# core.net
KiCad netlist of a schematic drawn in EAGLE
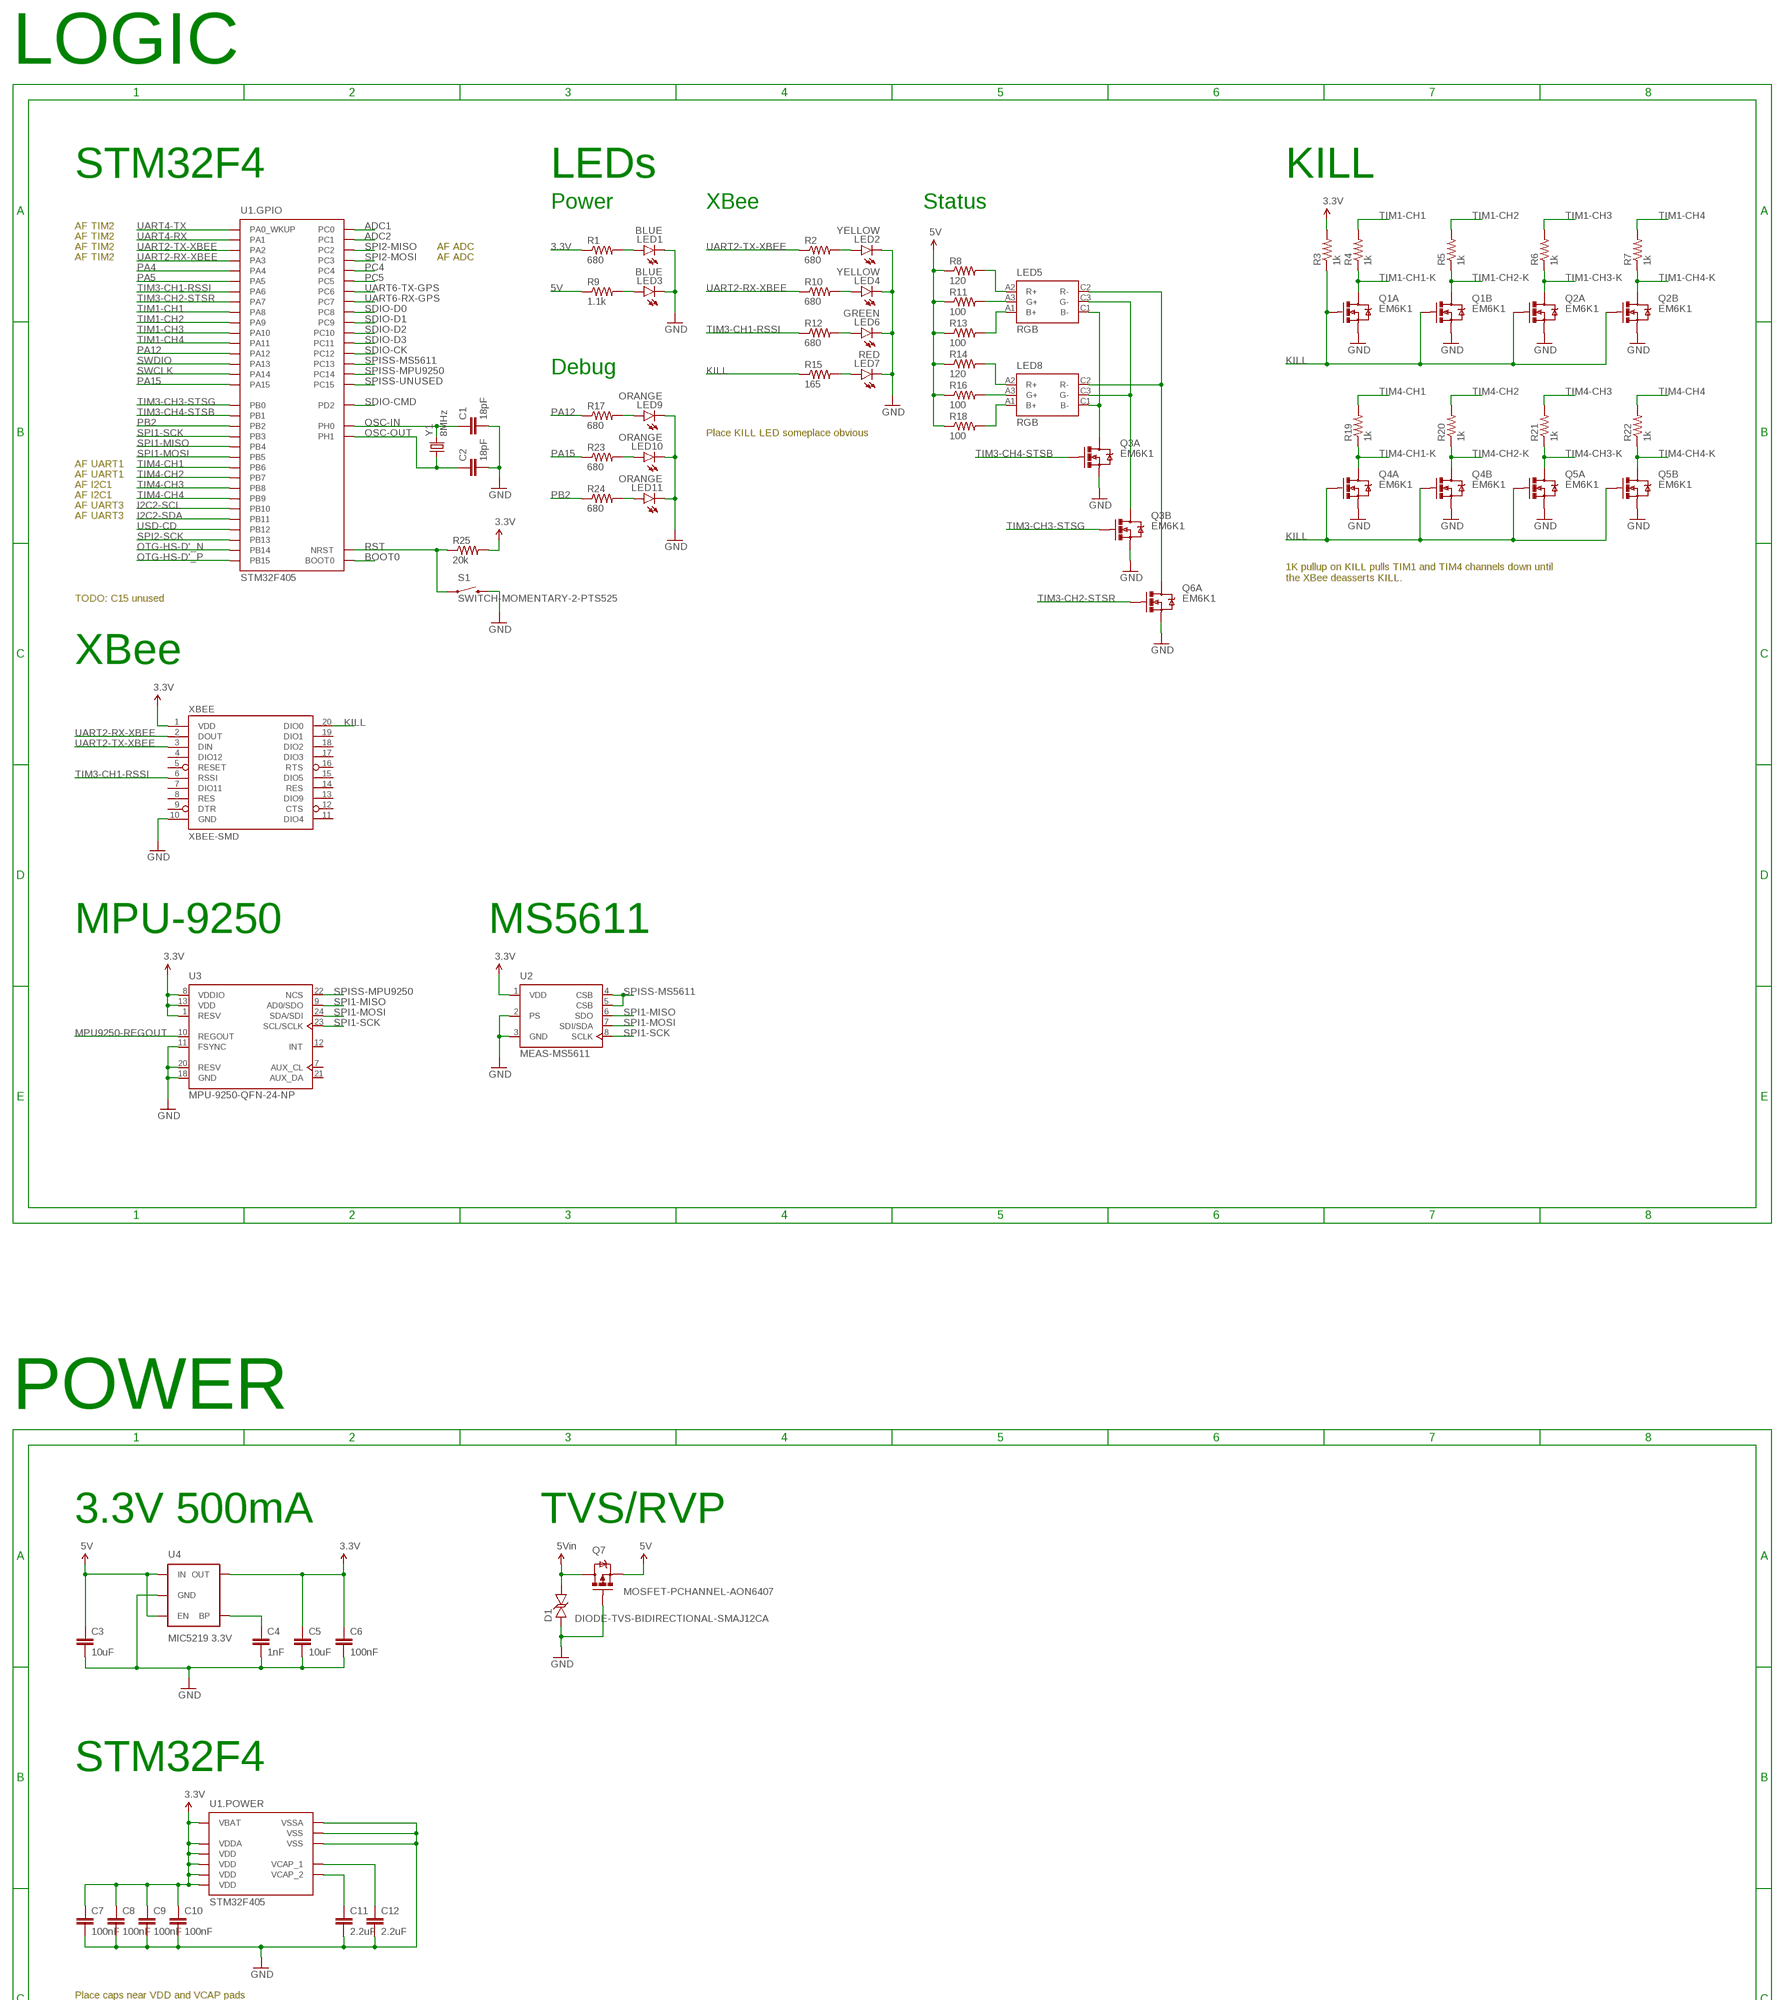
[diagram p0: schematic, sheet 1, part 1 of 2]
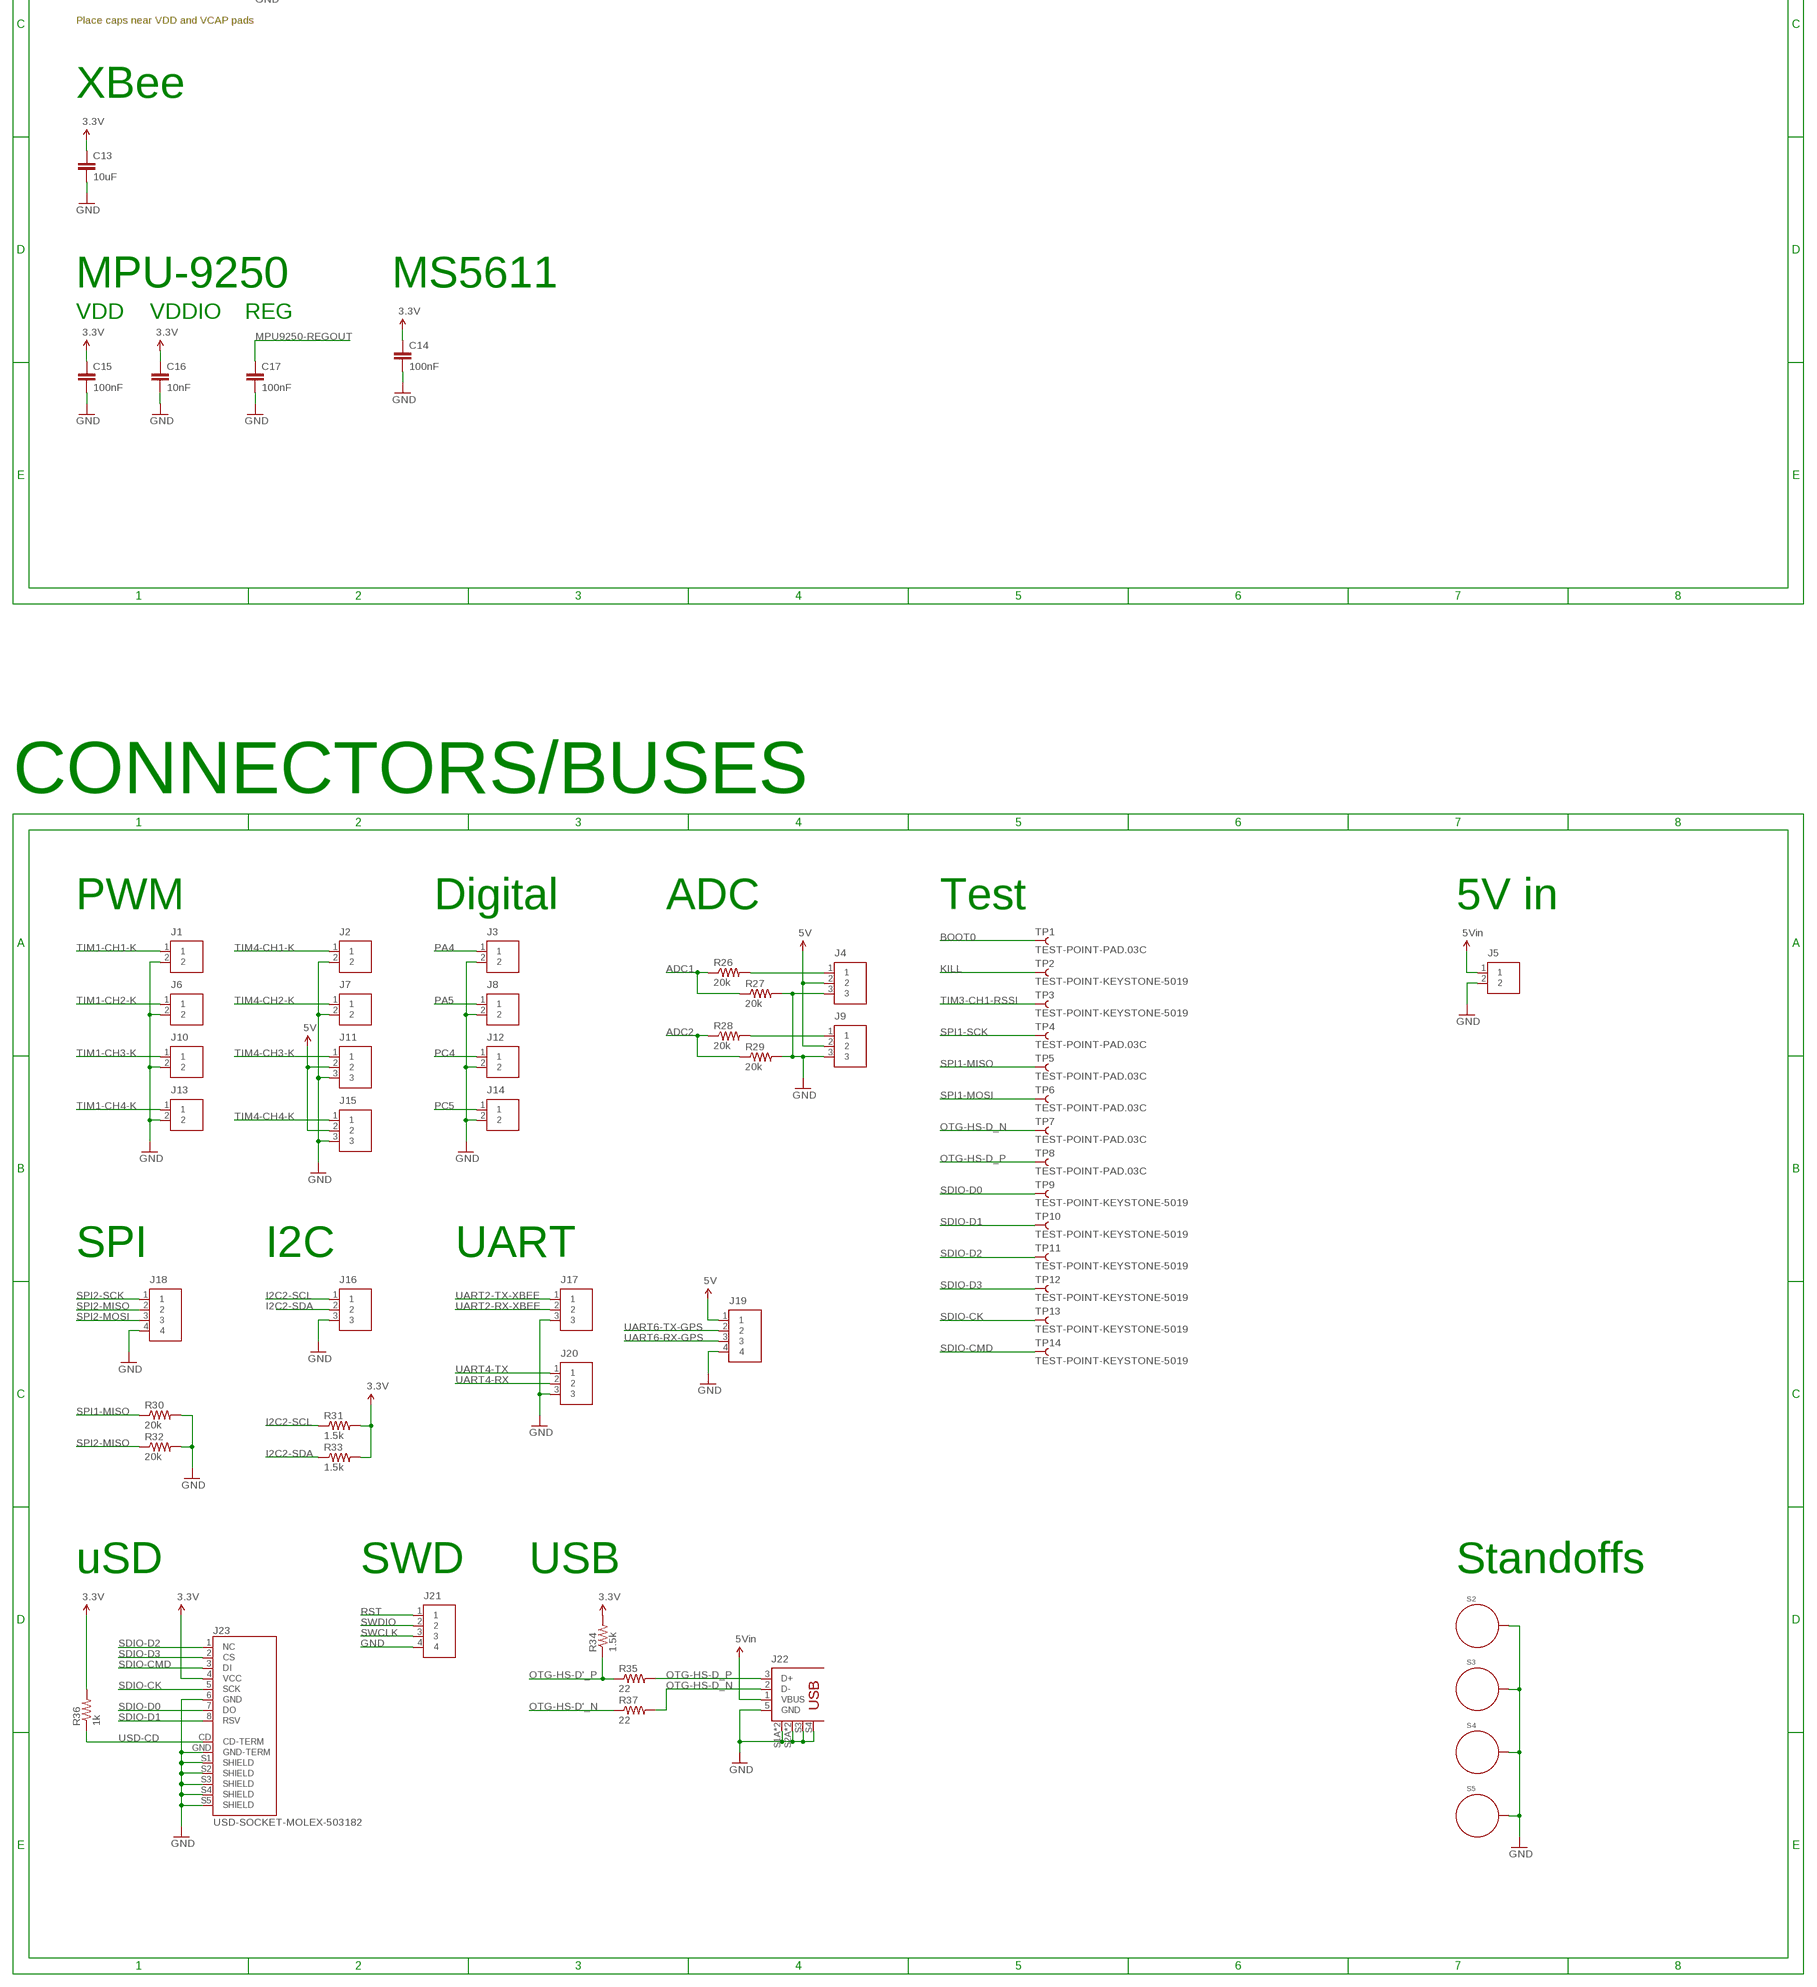
[diagram p1: schematic, sheet 1, part 2 of 2]

(export (version "E")
  (design (tool "Eeschema 10.0.6"))
  (components
    (comp (ref "C1")
      (value "18pF")
      (footprint "eagle-import:0603")
      (libsource (lib "eagle-import") (part "CAP-18PF-50V-5%(0603)"))
    )
    (comp (ref "C2")
      (value "18pF")
      (footprint "eagle-import:0603")
      (libsource (lib "eagle-import") (part "CAP-18PF-50V-5%(0603)"))
    )
    (comp (ref "C3")
      (value "10uF")
      (footprint "eagle-import:0805")
      (libsource (lib "eagle-import") (part "CAP-10UF-10V-10%(0805)"))
    )
    (comp (ref "C4")
      (value "1nF")
      (footprint "eagle-import:0603")
      (libsource (lib "eagle-import") (part "CAP-1NF-50V-10%(0603)"))
    )
    (comp (ref "C5")
      (value "10uF")
      (footprint "eagle-import:0805")
      (libsource (lib "eagle-import") (part "CAP-10UF-10V-10%(0805)"))
    )
    (comp (ref "C6")
      (value "100nF")
      (footprint "eagle-import:0603")
      (libsource (lib "eagle-import") (part "CAP-100NF-16V-10%(0603)"))
    )
    (comp (ref "C7")
      (value "100nF")
      (footprint "eagle-import:0603")
      (libsource (lib "eagle-import") (part "CAP-100NF-16V-10%(0603)"))
    )
    (comp (ref "C8")
      (value "100nF")
      (footprint "eagle-import:0603")
      (libsource (lib "eagle-import") (part "CAP-100NF-16V-10%(0603)"))
    )
    (comp (ref "C9")
      (value "100nF")
      (footprint "eagle-import:0603")
      (libsource (lib "eagle-import") (part "CAP-100NF-16V-10%(0603)"))
    )
    (comp (ref "C10")
      (value "100nF")
      (footprint "eagle-import:0603")
      (libsource (lib "eagle-import") (part "CAP-100NF-16V-10%(0603)"))
    )
    (comp (ref "C11")
      (value "2.2uF")
      (footprint "eagle-import:0603")
      (libsource (lib "eagle-import") (part "CAP-2.2UF-10V-10%(0603)"))
    )
    (comp (ref "C12")
      (value "2.2uF")
      (footprint "eagle-import:0603")
      (libsource (lib "eagle-import") (part "CAP-2.2UF-10V-10%(0603)"))
    )
    (comp (ref "C13")
      (value "10uF")
      (footprint "eagle-import:0805")
      (libsource (lib "eagle-import") (part "CAP-10UF-10V-10%(0805)"))
    )
    (comp (ref "C14")
      (value "100nF")
      (footprint "eagle-import:0603")
      (libsource (lib "eagle-import") (part "CAP-100NF-16V-10%(0603)"))
    )
    (comp (ref "C15")
      (value "100nF")
      (footprint "eagle-import:0603")
      (libsource (lib "eagle-import") (part "CAP-100NF-16V-10%(0603)"))
    )
    (comp (ref "C16")
      (value "10nF")
      (footprint "eagle-import:0603")
      (libsource (lib "eagle-import") (part "CAP-10NF-50V-10%(0603)"))
    )
    (comp (ref "C17")
      (value "100nF")
      (footprint "eagle-import:0603")
      (libsource (lib "eagle-import") (part "CAP-100NF-16V-10%(0603)"))
    )
    (comp (ref "D1")
      (value "DIODE-TVS-BIDIRECTIONAL-SMAJ12CA")
      (footprint "eagle-import:SMAJ")
      (libsource (lib "eagle-import") (part "DIODE-TVS-BIDIRECTIONAL-SMAJ12CA"))
    )
    (comp (ref "J1")
      (value "M02")
      (footprint "eagle-import:MOLEX-2MM-MICROLATCH-2POS-RA")
      (libsource (lib "eagle-import") (part "M02"))
    )
    (comp (ref "J2")
      (value "M02")
      (footprint "eagle-import:MOLEX-2MM-MICROLATCH-2POS-RA")
      (libsource (lib "eagle-import") (part "M02"))
    )
    (comp (ref "J3")
      (value "M02")
      (footprint "eagle-import:MOLEX-2MM-MICROLATCH-2POS-RA")
      (libsource (lib "eagle-import") (part "M02"))
    )
    (comp (ref "J4")
      (value "M03")
      (footprint "eagle-import:MOLEX-2MM-MICROLATCH-3POS-RA")
      (libsource (lib "eagle-import") (part "M03"))
    )
    (comp (ref "J5")
      (value "M02")
      (footprint "eagle-import:MOLEX-2MM-MICROLATCH-2POS-RA")
      (libsource (lib "eagle-import") (part "M02"))
    )
    (comp (ref "J6")
      (value "M02")
      (footprint "eagle-import:MOLEX-2MM-MICROLATCH-2POS-RA")
      (libsource (lib "eagle-import") (part "M02"))
    )
    (comp (ref "J7")
      (value "M02")
      (footprint "eagle-import:MOLEX-2MM-MICROLATCH-2POS-RA")
      (libsource (lib "eagle-import") (part "M02"))
    )
    (comp (ref "J8")
      (value "M02")
      (footprint "eagle-import:MOLEX-2MM-MICROLATCH-2POS-RA")
      (libsource (lib "eagle-import") (part "M02"))
    )
    (comp (ref "J9")
      (value "M03")
      (footprint "eagle-import:MOLEX-2MM-MICROLATCH-3POS-RA")
      (libsource (lib "eagle-import") (part "M03"))
    )
    (comp (ref "J10")
      (value "M02")
      (footprint "eagle-import:MOLEX-2MM-MICROLATCH-2POS-RA")
      (libsource (lib "eagle-import") (part "M02"))
    )
    (comp (ref "J11")
      (value "M03")
      (footprint "eagle-import:MOLEX-2MM-MICROLATCH-3POS-RA")
      (libsource (lib "eagle-import") (part "M03"))
    )
    (comp (ref "J12")
      (value "M02")
      (footprint "eagle-import:MOLEX-2MM-MICROLATCH-2POS-RA")
      (libsource (lib "eagle-import") (part "M02"))
    )
    (comp (ref "J13")
      (value "M02")
      (footprint "eagle-import:MOLEX-2MM-MICROLATCH-2POS-RA")
      (libsource (lib "eagle-import") (part "M02"))
    )
    (comp (ref "J14")
      (value "M02")
      (footprint "eagle-import:MOLEX-2MM-MICROLATCH-2POS-RA")
      (libsource (lib "eagle-import") (part "M02"))
    )
    (comp (ref "J15")
      (value "M03")
      (footprint "eagle-import:MOLEX-2MM-MICROLATCH-3POS-RA")
      (libsource (lib "eagle-import") (part "M03"))
    )
    (comp (ref "J16")
      (value "M03")
      (footprint "eagle-import:MOLEX-2MM-MICROLATCH-3POS-RA")
      (libsource (lib "eagle-import") (part "M03"))
    )
    (comp (ref "J17")
      (value "M03")
      (footprint "eagle-import:MOLEX-2MM-MICROLATCH-3POS-RA")
      (libsource (lib "eagle-import") (part "M03"))
    )
    (comp (ref "J18")
      (value "M04")
      (footprint "eagle-import:MOLEX-2MM-MICROLATCH-4POS-RA")
      (libsource (lib "eagle-import") (part "M04"))
    )
    (comp (ref "J19")
      (value "M04")
      (footprint "eagle-import:MOLEX-2MM-MICROLATCH-4POS-RA")
      (libsource (lib "eagle-import") (part "M04"))
    )
    (comp (ref "J20")
      (value "M03")
      (footprint "eagle-import:MOLEX-2MM-MICROLATCH-3POS-RA")
      (libsource (lib "eagle-import") (part "M03"))
    )
    (comp (ref "J21")
      (value "M04")
      (footprint "eagle-import:MOLEX-2MM-MICROLATCH-4POS-RA")
      (libsource (lib "eagle-import") (part "M04"))
    )
    (comp (ref "J22")
      (value "USB+SHIELD-MICROB-SMD-MOLEX")
      (footprint "eagle-import:USB-MICROB-SMD-MOLEX")
      (libsource (lib "eagle-import") (part "USB+SHIELD-MICROB-SMD-MOLEX"))
    )
    (comp (ref "J23")
      (value "USD-SOCKET-MOLEX-503182")
      (footprint "eagle-import:USD-SOCKET-PP-MOLEX-503182")
      (libsource (lib "eagle-import") (part "USD-SOCKET-MOLEX-503182"))
    )
    (comp (ref "LED1")
      (value "BLUE")
      (footprint "eagle-import:LED-0603")
      (libsource (lib "eagle-import") (part "LED-KINGBRIGHT-HELI-BLUE(0603)"))
    )
    (comp (ref "LED2")
      (value "YELLOW")
      (footprint "eagle-import:LED-0603")
      (libsource (lib "eagle-import") (part "LED-KINGBRIGHT-HELI-YELLOW(0603)"))
    )
    (comp (ref "LED3")
      (value "BLUE")
      (footprint "eagle-import:LED-0603")
      (libsource (lib "eagle-import") (part "LED-KINGBRIGHT-HELI-BLUE(0603)"))
    )
    (comp (ref "LED4")
      (value "YELLOW")
      (footprint "eagle-import:LED-0603")
      (libsource (lib "eagle-import") (part "LED-KINGBRIGHT-HELI-YELLOW(0603)"))
    )
    (comp (ref "LED5")
      (value "RGB")
      (footprint "eagle-import:PLCC-6")
      (libsource (lib "eagle-import") (part "OSRAM-MULTILED-RGB"))
    )
    (comp (ref "LED6")
      (value "GREEN")
      (footprint "eagle-import:LED-0603")
      (libsource (lib "eagle-import") (part "LED-KINGBRIGHT-HELI-GREEN(0603)"))
    )
    (comp (ref "LED7")
      (value "RED")
      (footprint "eagle-import:LED-0603")
      (libsource (lib "eagle-import") (part "LED-KINGBRIGHT-HELI-RED(0603)"))
    )
    (comp (ref "LED8")
      (value "RGB")
      (footprint "eagle-import:PLCC-6")
      (libsource (lib "eagle-import") (part "OSRAM-MULTILED-RGB"))
    )
    (comp (ref "LED9")
      (value "ORANGE")
      (footprint "eagle-import:LED-0603")
      (libsource (lib "eagle-import") (part "LED-KINGBRIGHT-HELI-ORANGE(0603)"))
    )
    (comp (ref "LED10")
      (value "ORANGE")
      (footprint "eagle-import:LED-0603")
      (libsource (lib "eagle-import") (part "LED-KINGBRIGHT-HELI-ORANGE(0603)"))
    )
    (comp (ref "LED11")
      (value "ORANGE")
      (footprint "eagle-import:LED-0603")
      (libsource (lib "eagle-import") (part "LED-KINGBRIGHT-HELI-ORANGE(0603)"))
    )
    (comp (ref "Q1")
      (value "EM6K1")
      (footprint "eagle-import:SOT-666")
      (libsource (lib "eagle-import") (part "MOSFET-NCHANNEL-DUAL-EM6K1"))
    )
    (comp (ref "Q2")
      (value "EM6K1")
      (footprint "eagle-import:SOT-666")
      (libsource (lib "eagle-import") (part "MOSFET-NCHANNEL-DUAL-EM6K1"))
    )
    (comp (ref "Q3")
      (value "EM6K1")
      (footprint "eagle-import:SOT-666")
      (libsource (lib "eagle-import") (part "MOSFET-NCHANNEL-DUAL-EM6K1"))
    )
    (comp (ref "Q4")
      (value "EM6K1")
      (footprint "eagle-import:SOT-666")
      (libsource (lib "eagle-import") (part "MOSFET-NCHANNEL-DUAL-EM6K1"))
    )
    (comp (ref "Q5")
      (value "EM6K1")
      (footprint "eagle-import:SOT-666")
      (libsource (lib "eagle-import") (part "MOSFET-NCHANNEL-DUAL-EM6K1"))
    )
    (comp (ref "Q6")
      (value "EM6K1")
      (footprint "eagle-import:SOT-666")
      (libsource (lib "eagle-import") (part "MOSFET-NCHANNEL-DUAL-EM6K1"))
    )
    (comp (ref "Q7")
      (value "MOSFET-PCHANNEL-AON6407")
      (footprint "eagle-import:DFN5X6")
      (libsource (lib "eagle-import") (part "MOSFET-PCHANNEL-AON6407"))
    )
    (comp (ref "R1")
      (value "680")
      (footprint "eagle-import:0603")
      (libsource (lib "eagle-import") (part "RES-680OHM-0.1W-5%(0603)"))
    )
    (comp (ref "R2")
      (value "680")
      (footprint "eagle-import:0603")
      (libsource (lib "eagle-import") (part "RES-680OHM-0.1W-5%(0603)"))
    )
    (comp (ref "R3")
      (value "1k")
      (footprint "eagle-import:0603")
      (libsource (lib "eagle-import") (part "RES-1KOHM-0.1W-5%(0603)"))
    )
    (comp (ref "R4")
      (value "1k")
      (footprint "eagle-import:0603")
      (libsource (lib "eagle-import") (part "RES-1KOHM-0.1W-5%(0603)"))
    )
    (comp (ref "R5")
      (value "1k")
      (footprint "eagle-import:0603")
      (libsource (lib "eagle-import") (part "RES-1KOHM-0.1W-5%(0603)"))
    )
    (comp (ref "R6")
      (value "1k")
      (footprint "eagle-import:0603")
      (libsource (lib "eagle-import") (part "RES-1KOHM-0.1W-5%(0603)"))
    )
    (comp (ref "R7")
      (value "1k")
      (footprint "eagle-import:0603")
      (libsource (lib "eagle-import") (part "RES-1KOHM-0.1W-5%(0603)"))
    )
    (comp (ref "R8")
      (value "120")
      (footprint "eagle-import:0603")
      (libsource (lib "eagle-import") (part "RES-120OHM-0.1W-5%(0603)"))
    )
    (comp (ref "R9")
      (value "1.1k")
      (footprint "eagle-import:0603")
      (libsource (lib "eagle-import") (part "RES-1.1KOHM-0.1W-5%(0603)"))
    )
    (comp (ref "R10")
      (value "680")
      (footprint "eagle-import:0603")
      (libsource (lib "eagle-import") (part "RES-680OHM-0.1W-5%(0603)"))
    )
    (comp (ref "R11")
      (value "100")
      (footprint "eagle-import:0603")
      (libsource (lib "eagle-import") (part "RES-100OHM-0.1W-5%(0603)"))
    )
    (comp (ref "R12")
      (value "680")
      (footprint "eagle-import:0603")
      (libsource (lib "eagle-import") (part "RES-680OHM-0.1W-5%(0603)"))
    )
    (comp (ref "R13")
      (value "100")
      (footprint "eagle-import:0603")
      (libsource (lib "eagle-import") (part "RES-100OHM-0.1W-5%(0603)"))
    )
    (comp (ref "R14")
      (value "120")
      (footprint "eagle-import:0603")
      (libsource (lib "eagle-import") (part "RES-120OHM-0.1W-5%(0603)"))
    )
    (comp (ref "R15")
      (value "165")
      (footprint "eagle-import:0603")
      (libsource (lib "eagle-import") (part "RES-165OHM-0.1W-1%(0603)"))
    )
    (comp (ref "R16")
      (value "100")
      (footprint "eagle-import:0603")
      (libsource (lib "eagle-import") (part "RES-100OHM-0.1W-5%(0603)"))
    )
    (comp (ref "R17")
      (value "680")
      (footprint "eagle-import:0603")
      (libsource (lib "eagle-import") (part "RES-680OHM-0.1W-5%(0603)"))
    )
    (comp (ref "R18")
      (value "100")
      (footprint "eagle-import:0603")
      (libsource (lib "eagle-import") (part "RES-100OHM-0.1W-5%(0603)"))
    )
    (comp (ref "R19")
      (value "1k")
      (footprint "eagle-import:0603")
      (libsource (lib "eagle-import") (part "RES-1KOHM-0.1W-5%(0603)"))
    )
    (comp (ref "R20")
      (value "1k")
      (footprint "eagle-import:0603")
      (libsource (lib "eagle-import") (part "RES-1KOHM-0.1W-5%(0603)"))
    )
    (comp (ref "R21")
      (value "1k")
      (footprint "eagle-import:0603")
      (libsource (lib "eagle-import") (part "RES-1KOHM-0.1W-5%(0603)"))
    )
    (comp (ref "R22")
      (value "1k")
      (footprint "eagle-import:0603")
      (libsource (lib "eagle-import") (part "RES-1KOHM-0.1W-5%(0603)"))
    )
    (comp (ref "R23")
      (value "680")
      (footprint "eagle-import:0603")
      (libsource (lib "eagle-import") (part "RES-680OHM-0.1W-5%(0603)"))
    )
    (comp (ref "R24")
      (value "680")
      (footprint "eagle-import:0603")
      (libsource (lib "eagle-import") (part "RES-680OHM-0.1W-5%(0603)"))
    )
    (comp (ref "R25")
      (value "20k")
      (footprint "eagle-import:0603")
      (libsource (lib "eagle-import") (part "RES-20KOHM-0.1W-1%(0603)"))
    )
    (comp (ref "R26")
      (value "20k")
      (footprint "eagle-import:0603")
      (libsource (lib "eagle-import") (part "RES-20KOHM-0.1W-0.1%(0603)"))
    )
    (comp (ref "R27")
      (value "20k")
      (footprint "eagle-import:0603")
      (libsource (lib "eagle-import") (part "RES-20KOHM-0.1W-0.1%(0603)"))
    )
    (comp (ref "R28")
      (value "20k")
      (footprint "eagle-import:0603")
      (libsource (lib "eagle-import") (part "RES-20KOHM-0.1W-0.1%(0603)"))
    )
    (comp (ref "R29")
      (value "20k")
      (footprint "eagle-import:0603")
      (libsource (lib "eagle-import") (part "RES-20KOHM-0.1W-0.1%(0603)"))
    )
    (comp (ref "R30")
      (value "20k")
      (footprint "eagle-import:0603")
      (libsource (lib "eagle-import") (part "RES-20KOHM-0.1W-1%(0603)"))
    )
    (comp (ref "R31")
      (value "1.5k")
      (footprint "eagle-import:0603")
      (libsource (lib "eagle-import") (part "RES-1.5KOHM-0.1W-5%(0603)"))
    )
    (comp (ref "R32")
      (value "20k")
      (footprint "eagle-import:0603")
      (libsource (lib "eagle-import") (part "RES-20KOHM-0.1W-1%(0603)"))
    )
    (comp (ref "R33")
      (value "1.5k")
      (footprint "eagle-import:0603")
      (libsource (lib "eagle-import") (part "RES-1.5KOHM-0.1W-5%(0603)"))
    )
    (comp (ref "R34")
      (value "1.5k")
      (footprint "eagle-import:0603")
      (libsource (lib "eagle-import") (part "RES-1.5KOHM-0.1W-5%(0603)"))
    )
    (comp (ref "R35")
      (value "22")
      (footprint "eagle-import:0603")
      (libsource (lib "eagle-import") (part "RES-22OHM-0.1W-5%(0603)"))
    )
    (comp (ref "R36")
      (value "1k")
      (footprint "eagle-import:0603")
      (libsource (lib "eagle-import") (part "RES-1KOHM-0.1W-5%(0603)"))
    )
    (comp (ref "R37")
      (value "22")
      (footprint "eagle-import:0603")
      (libsource (lib "eagle-import") (part "RES-22OHM-0.1W-5%(0603)"))
    )
    (comp (ref "S1")
      (value "SWITCH-MOMENTARY-2-PTS525")
      (footprint "eagle-import:TACTILE-SWITCH-SMD")
      (libsource (lib "eagle-import") (part "SWITCH-MOMENTARY-2-PTS525"))
    )
    (comp (ref "S2")
      (value "STANDOFF_ELECTRICAL-#4")
      (footprint "eagle-import:STANDOFF-ELECTRICAL-#4")
      (libsource (lib "eagle-import") (part "STANDOFF_ELECTRICAL-#4"))
    )
    (comp (ref "S3")
      (value "STANDOFF_ELECTRICAL-#4")
      (footprint "eagle-import:STANDOFF-ELECTRICAL-#4")
      (libsource (lib "eagle-import") (part "STANDOFF_ELECTRICAL-#4"))
    )
    (comp (ref "S4")
      (value "STANDOFF_ELECTRICAL-#4")
      (footprint "eagle-import:STANDOFF-ELECTRICAL-#4")
      (libsource (lib "eagle-import") (part "STANDOFF_ELECTRICAL-#4"))
    )
    (comp (ref "S5")
      (value "STANDOFF_ELECTRICAL-#4")
      (footprint "eagle-import:STANDOFF-ELECTRICAL-#4")
      (libsource (lib "eagle-import") (part "STANDOFF_ELECTRICAL-#4"))
    )
    (comp (ref "TP1")
      (value "TEST-POINT-PAD.03C")
      (footprint "eagle-import:PAD-.03C")
      (libsource (lib "eagle-import") (part "TEST-POINT-PAD.03C"))
    )
    (comp (ref "TP2")
      (value "TEST-POINT-KEYSTONE-5019")
      (footprint "eagle-import:PAD.15X.08")
      (libsource (lib "eagle-import") (part "TEST-POINT-KEYSTONE-5019"))
    )
    (comp (ref "TP3")
      (value "TEST-POINT-KEYSTONE-5019")
      (footprint "eagle-import:PAD.15X.08")
      (libsource (lib "eagle-import") (part "TEST-POINT-KEYSTONE-5019"))
    )
    (comp (ref "TP4")
      (value "TEST-POINT-PAD.03C")
      (footprint "eagle-import:PAD-.03C")
      (libsource (lib "eagle-import") (part "TEST-POINT-PAD.03C"))
    )
    (comp (ref "TP5")
      (value "TEST-POINT-PAD.03C")
      (footprint "eagle-import:PAD-.03C")
      (libsource (lib "eagle-import") (part "TEST-POINT-PAD.03C"))
    )
    (comp (ref "TP6")
      (value "TEST-POINT-PAD.03C")
      (footprint "eagle-import:PAD-.03C")
      (libsource (lib "eagle-import") (part "TEST-POINT-PAD.03C"))
    )
    (comp (ref "TP7")
      (value "TEST-POINT-PAD.03C")
      (footprint "eagle-import:PAD-.03C")
      (libsource (lib "eagle-import") (part "TEST-POINT-PAD.03C"))
    )
    (comp (ref "TP8")
      (value "TEST-POINT-PAD.03C")
      (footprint "eagle-import:PAD-.03C")
      (libsource (lib "eagle-import") (part "TEST-POINT-PAD.03C"))
    )
    (comp (ref "TP9")
      (value "TEST-POINT-KEYSTONE-5019")
      (footprint "eagle-import:PAD.15X.08")
      (libsource (lib "eagle-import") (part "TEST-POINT-KEYSTONE-5019"))
    )
    (comp (ref "TP10")
      (value "TEST-POINT-KEYSTONE-5019")
      (footprint "eagle-import:PAD.15X.08")
      (libsource (lib "eagle-import") (part "TEST-POINT-KEYSTONE-5019"))
    )
    (comp (ref "TP11")
      (value "TEST-POINT-KEYSTONE-5019")
      (footprint "eagle-import:PAD.15X.08")
      (libsource (lib "eagle-import") (part "TEST-POINT-KEYSTONE-5019"))
    )
    (comp (ref "TP12")
      (value "TEST-POINT-KEYSTONE-5019")
      (footprint "eagle-import:PAD.15X.08")
      (libsource (lib "eagle-import") (part "TEST-POINT-KEYSTONE-5019"))
    )
    (comp (ref "TP13")
      (value "TEST-POINT-KEYSTONE-5019")
      (footprint "eagle-import:PAD.15X.08")
      (libsource (lib "eagle-import") (part "TEST-POINT-KEYSTONE-5019"))
    )
    (comp (ref "TP14")
      (value "TEST-POINT-KEYSTONE-5019")
      (footprint "eagle-import:PAD.15X.08")
      (libsource (lib "eagle-import") (part "TEST-POINT-KEYSTONE-5019"))
    )
    (comp (ref "U1")
      (value "STM32F405")
      (footprint "eagle-import:LQFP-64-STM32F405")
      (libsource (lib "eagle-import") (part "STM32F405"))
    )
    (comp (ref "U2")
      (value "MEAS-MS5611")
      (footprint "eagle-import:MEAS-MS5611")
      (libsource (lib "eagle-import") (part "MEAS-MS5611"))
    )
    (comp (ref "U3")
      (value "MPU-9250-QFN-24-NP")
      (footprint "eagle-import:QFN-24-NP-3X3MM")
      (libsource (lib "eagle-import") (part "MPU-9250-QFN-24-NP"))
    )
    (comp (ref "U4")
      (value "MIC5219 3.3V")
      (footprint "eagle-import:SOT23-5")
      (libsource (lib "eagle-import") (part "V-REG-MIC5219-3.3V"))
    )
    (comp (ref "XBEE")
      (value "XBEE-SMD")
      (footprint "eagle-import:XBEE-SMD")
      (libsource (lib "eagle-import") (part "XBEE-SMD"))
    )
    (comp (ref "Y1")
      (value "8MHz")
      (footprint "eagle-import:CX532")
      (libsource (lib "eagle-import") (part "CRYSTAL-8MHZ-CX532"))
    )
  )
  (nets
    (net (code "1") (name "/ADC1") (class "Default")
      (node (ref "R26") (pin "1") (pinfunction "1_1") (pintype "passive"))
      (node (ref "R27") (pin "1") (pinfunction "1_1") (pintype "passive"))
      (node (ref "U1") (pin "8") (pinfunction "PC0_8") (pintype "bidirectional"))
    )
    (net (code "2") (name "/ADC2") (class "Default")
      (node (ref "R28") (pin "1") (pinfunction "1_1") (pintype "passive"))
      (node (ref "R29") (pin "1") (pinfunction "1_1") (pintype "passive"))
      (node (ref "U1") (pin "9") (pinfunction "PC1_9") (pintype "bidirectional"))
    )
    (net (code "3") (name "/BOOT0") (class "Default")
      (node (ref "TP1") (pin "1") (pinfunction "1_1") (pintype "bidirectional"))
      (node (ref "U1") (pin "60") (pinfunction "BOOT0_60") (pintype "bidirectional"))
    )
    (net (code "4") (name "/I2C2-SCL") (class "Default")
      (node (ref "J16") (pin "1") (pinfunction "1_1") (pintype "bidirectional"))
      (node (ref "R31") (pin "1") (pinfunction "1_1") (pintype "passive"))
      (node (ref "U1") (pin "29") (pinfunction "PB10_29") (pintype "bidirectional"))
    )
    (net (code "5") (name "/I2C2-SDA") (class "Default")
      (node (ref "J16") (pin "2") (pinfunction "2_2") (pintype "bidirectional"))
      (node (ref "R33") (pin "1") (pinfunction "1_1") (pintype "passive"))
      (node (ref "U1") (pin "30") (pinfunction "PB11_30") (pintype "bidirectional"))
    )
    (net (code "6") (name "/KILL") (class "Default")
      (node (ref "Q1") (pin "2") (pinfunction "G_2") (pintype "passive"))
      (node (ref "Q1") (pin "5") (pinfunction "G_5") (pintype "passive"))
      (node (ref "Q2") (pin "2") (pinfunction "G_2") (pintype "passive"))
      (node (ref "Q2") (pin "5") (pinfunction "G_5") (pintype "passive"))
      (node (ref "Q4") (pin "2") (pinfunction "G_2") (pintype "passive"))
      (node (ref "Q4") (pin "5") (pinfunction "G_5") (pintype "passive"))
      (node (ref "Q5") (pin "2") (pinfunction "G_2") (pintype "passive"))
      (node (ref "Q5") (pin "5") (pinfunction "G_5") (pintype "passive"))
      (node (ref "R15") (pin "1") (pinfunction "1_1") (pintype "passive"))
      (node (ref "R3") (pin "1") (pinfunction "1_1") (pintype "passive"))
      (node (ref "TP2") (pin "1") (pinfunction "1_1") (pintype "bidirectional"))
      (node (ref "XBEE") (pin "20") (pinfunction "DIO0_20") (pintype "bidirectional"))
    )
    (net (code "7") (name "/MPU9250-REGOUT") (class "Default")
      (node (ref "C17") (pin "2") (pinfunction "2_2") (pintype "passive"))
      (node (ref "U3") (pin "10") (pinfunction "REGOUT_10") (pintype "bidirectional"))
    )
    (net (code "8") (name "/OSC-IN") (class "Default")
      (node (ref "C1") (pin "2") (pinfunction "2_2") (pintype "passive"))
      (node (ref "U1") (pin "5") (pinfunction "PH0_5") (pintype "bidirectional"))
      (node (ref "Y1") (pin "2") (pinfunction "2_2") (pintype "passive"))
    )
    (net (code "9") (name "/OSC-OUT") (class "Default")
      (node (ref "C2") (pin "2") (pinfunction "2_2") (pintype "passive"))
      (node (ref "U1") (pin "6") (pinfunction "PH1_6") (pintype "bidirectional"))
      (node (ref "Y1") (pin "1") (pinfunction "1_1") (pintype "passive"))
    )
    (net (code "10") (name "/OTG-HS-D'_N") (class "Default")
      (node (ref "R37") (pin "1") (pinfunction "1_1") (pintype "passive"))
      (node (ref "U1") (pin "35") (pinfunction "PB14_35") (pintype "bidirectional"))
    )
    (net (code "11") (name "/OTG-HS-D'_P") (class "Default")
      (node (ref "R34") (pin "1") (pinfunction "1_1") (pintype "passive"))
      (node (ref "R35") (pin "1") (pinfunction "1_1") (pintype "passive"))
      (node (ref "U1") (pin "36") (pinfunction "PB15_36") (pintype "bidirectional"))
    )
    (net (code "12") (name "/OTG-HS-D_N") (class "Default")
      (node (ref "J22") (pin "2") (pinfunction "D-_2") (pintype "bidirectional"))
      (node (ref "R37") (pin "2") (pinfunction "2_2") (pintype "passive"))
      (node (ref "TP7") (pin "1") (pinfunction "1_1") (pintype "bidirectional"))
    )
    (net (code "13") (name "/OTG-HS-D_P") (class "Default")
      (node (ref "J22") (pin "3") (pinfunction "D+_3") (pintype "bidirectional"))
      (node (ref "R35") (pin "2") (pinfunction "2_2") (pintype "passive"))
      (node (ref "TP8") (pin "1") (pinfunction "1_1") (pintype "bidirectional"))
    )
    (net (code "14") (name "/PA4") (class "Default")
      (node (ref "J3") (pin "1") (pinfunction "1_1") (pintype "bidirectional"))
      (node (ref "U1") (pin "20") (pinfunction "PA4_20") (pintype "bidirectional"))
    )
    (net (code "15") (name "/PA5") (class "Default")
      (node (ref "J8") (pin "1") (pinfunction "1_1") (pintype "bidirectional"))
      (node (ref "U1") (pin "21") (pinfunction "PA5_21") (pintype "bidirectional"))
    )
    (net (code "16") (name "/PA12") (class "Default")
      (node (ref "R17") (pin "1") (pinfunction "1_1") (pintype "passive"))
      (node (ref "U1") (pin "45") (pinfunction "PA12_45") (pintype "bidirectional"))
    )
    (net (code "17") (name "/PA15") (class "Default")
      (node (ref "R23") (pin "1") (pinfunction "1_1") (pintype "passive"))
      (node (ref "U1") (pin "50") (pinfunction "PA15_50") (pintype "bidirectional"))
    )
    (net (code "18") (name "/PB2") (class "Default")
      (node (ref "R24") (pin "1") (pinfunction "1_1") (pintype "passive"))
      (node (ref "U1") (pin "28") (pinfunction "PB2_28") (pintype "bidirectional"))
    )
    (net (code "19") (name "/PC4") (class "Default")
      (node (ref "J12") (pin "1") (pinfunction "1_1") (pintype "bidirectional"))
      (node (ref "U1") (pin "24") (pinfunction "PC4_24") (pintype "bidirectional"))
    )
    (net (code "20") (name "/PC5") (class "Default")
      (node (ref "J14") (pin "1") (pinfunction "1_1") (pintype "bidirectional"))
      (node (ref "U1") (pin "25") (pinfunction "PC5_25") (pintype "bidirectional"))
    )
    (net (code "21") (name "/RST") (class "Default")
      (node (ref "J21") (pin "1") (pinfunction "1_1") (pintype "bidirectional"))
      (node (ref "R25") (pin "1") (pinfunction "1_1") (pintype "passive"))
      (node (ref "S1") (pin "1") (pinfunction "1_1") (pintype "passive"))
      (node (ref "S1") (pin "2") (pinfunction "1_2") (pintype "passive"))
      (node (ref "U1") (pin "7") (pinfunction "NRST_7") (pintype "bidirectional"))
    )
    (net (code "22") (name "/SDIO-CK") (class "Default")
      (node (ref "J23") (pin "5") (pinfunction "SCK_5") (pintype "bidirectional"))
      (node (ref "TP13") (pin "1") (pinfunction "1_1") (pintype "bidirectional"))
      (node (ref "U1") (pin "53") (pinfunction "PC12_53") (pintype "bidirectional"))
    )
    (net (code "23") (name "/SDIO-CMD") (class "Default")
      (node (ref "J23") (pin "3") (pinfunction "DI_3") (pintype "bidirectional"))
      (node (ref "TP14") (pin "1") (pinfunction "1_1") (pintype "bidirectional"))
      (node (ref "U1") (pin "54") (pinfunction "PD2_54") (pintype "bidirectional"))
    )
    (net (code "24") (name "/SDIO-D0") (class "Default")
      (node (ref "J23") (pin "7") (pinfunction "DO_7") (pintype "bidirectional"))
      (node (ref "TP9") (pin "1") (pinfunction "1_1") (pintype "bidirectional"))
      (node (ref "U1") (pin "39") (pinfunction "PC8_39") (pintype "bidirectional"))
    )
    (net (code "25") (name "/SDIO-D1") (class "Default")
      (node (ref "J23") (pin "8") (pinfunction "RSV_8") (pintype "bidirectional"))
      (node (ref "TP10") (pin "1") (pinfunction "1_1") (pintype "bidirectional"))
      (node (ref "U1") (pin "40") (pinfunction "PC9_40") (pintype "bidirectional"))
    )
    (net (code "26") (name "/SDIO-D2") (class "Default")
      (node (ref "J23") (pin "1") (pinfunction "NC_1") (pintype "bidirectional"))
      (node (ref "TP11") (pin "1") (pinfunction "1_1") (pintype "bidirectional"))
      (node (ref "U1") (pin "51") (pinfunction "PC10_51") (pintype "bidirectional"))
    )
    (net (code "27") (name "/SDIO-D3") (class "Default")
      (node (ref "J23") (pin "2") (pinfunction "CS_2") (pintype "bidirectional"))
      (node (ref "TP12") (pin "1") (pinfunction "1_1") (pintype "bidirectional"))
      (node (ref "U1") (pin "52") (pinfunction "PC11_52") (pintype "bidirectional"))
    )
    (net (code "28") (name "/SPI1-MISO") (class "Default")
      (node (ref "R30") (pin "1") (pinfunction "1_1") (pintype "passive"))
      (node (ref "TP5") (pin "1") (pinfunction "1_1") (pintype "bidirectional"))
      (node (ref "U1") (pin "56") (pinfunction "PB4_56") (pintype "bidirectional"))
      (node (ref "U2") (pin "6") (pinfunction "SDO_6") (pintype "output"))
      (node (ref "U3") (pin "9") (pinfunction "AD0/SDO_9") (pintype "bidirectional"))
    )
    (net (code "29") (name "/SPI1-MOSI") (class "Default")
      (node (ref "TP6") (pin "1") (pinfunction "1_1") (pintype "bidirectional"))
      (node (ref "U1") (pin "57") (pinfunction "PB5_57") (pintype "bidirectional"))
      (node (ref "U2") (pin "7") (pinfunction "SDI/SDA_7") (pintype "bidirectional"))
      (node (ref "U3") (pin "24") (pinfunction "SDA/SDI_24") (pintype "bidirectional"))
    )
    (net (code "30") (name "/SPI1-SCK") (class "Default")
      (node (ref "TP4") (pin "1") (pinfunction "1_1") (pintype "bidirectional"))
      (node (ref "U1") (pin "55") (pinfunction "PB3_55") (pintype "bidirectional"))
      (node (ref "U2") (pin "8") (pinfunction "SCLK_8") (pintype "input"))
      (node (ref "U3") (pin "23") (pinfunction "SCL/SCLK_23") (pintype "bidirectional"))
    )
    (net (code "31") (name "/SPI2-MISO") (class "Default")
      (node (ref "J18") (pin "2") (pinfunction "2_2") (pintype "bidirectional"))
      (node (ref "R32") (pin "1") (pinfunction "1_1") (pintype "passive"))
      (node (ref "U1") (pin "10") (pinfunction "PC2_10") (pintype "bidirectional"))
    )
    (net (code "32") (name "/SPI2-MOSI") (class "Default")
      (node (ref "J18") (pin "3") (pinfunction "3_3") (pintype "bidirectional"))
      (node (ref "U1") (pin "11") (pinfunction "PC3_11") (pintype "bidirectional"))
    )
    (net (code "33") (name "/SPI2-SCK") (class "Default")
      (node (ref "J18") (pin "1") (pinfunction "1_1") (pintype "bidirectional"))
      (node (ref "U1") (pin "34") (pinfunction "PB13_34") (pintype "bidirectional"))
    )
    (net (code "34") (name "/SPISS-MPU9250") (class "Default")
      (node (ref "U1") (pin "3") (pinfunction "PC14_3") (pintype "bidirectional"))
      (node (ref "U3") (pin "22") (pinfunction "NCS_22") (pintype "bidirectional"))
    )
    (net (code "35") (name "/SPISS-MS5611") (class "Default")
      (node (ref "U1") (pin "2") (pinfunction "PC13_2") (pintype "bidirectional"))
      (node (ref "U2") (pin "4") (pinfunction "CSB_4") (pintype "input"))
      (node (ref "U2") (pin "5") (pinfunction "CSB_5") (pintype "input"))
    )
    (net (code "36") (name "/SPISS-UNUSED") (class "Default")
      (node (ref "U1") (pin "4") (pinfunction "PC15_4") (pintype "bidirectional"))
    )
    (net (code "37") (name "/SWCLK") (class "Default")
      (node (ref "J21") (pin "3") (pinfunction "3_3") (pintype "bidirectional"))
      (node (ref "U1") (pin "49") (pinfunction "PA14_49") (pintype "bidirectional"))
    )
    (net (code "38") (name "/SWDIO") (class "Default")
      (node (ref "J21") (pin "2") (pinfunction "2_2") (pintype "bidirectional"))
      (node (ref "U1") (pin "46") (pinfunction "PA13_46") (pintype "bidirectional"))
    )
    (net (code "39") (name "/TIM1-CH1") (class "Default")
      (node (ref "R4") (pin "2") (pinfunction "2_2") (pintype "passive"))
      (node (ref "U1") (pin "41") (pinfunction "PA8_41") (pintype "bidirectional"))
    )
    (net (code "40") (name "/TIM1-CH1-K") (class "Default")
      (node (ref "J1") (pin "1") (pinfunction "1_1") (pintype "bidirectional"))
      (node (ref "Q1") (pin "6") (pinfunction "D_6") (pintype "passive"))
      (node (ref "R4") (pin "1") (pinfunction "1_1") (pintype "passive"))
    )
    (net (code "41") (name "/TIM1-CH2") (class "Default")
      (node (ref "R5") (pin "2") (pinfunction "2_2") (pintype "passive"))
      (node (ref "U1") (pin "42") (pinfunction "PA9_42") (pintype "bidirectional"))
    )
    (net (code "42") (name "/TIM1-CH2-K") (class "Default")
      (node (ref "J6") (pin "1") (pinfunction "1_1") (pintype "bidirectional"))
      (node (ref "Q1") (pin "3") (pinfunction "D_3") (pintype "passive"))
      (node (ref "R5") (pin "1") (pinfunction "1_1") (pintype "passive"))
    )
    (net (code "43") (name "/TIM1-CH3") (class "Default")
      (node (ref "R6") (pin "2") (pinfunction "2_2") (pintype "passive"))
      (node (ref "U1") (pin "43") (pinfunction "PA10_43") (pintype "bidirectional"))
    )
    (net (code "44") (name "/TIM1-CH3-K") (class "Default")
      (node (ref "J10") (pin "1") (pinfunction "1_1") (pintype "bidirectional"))
      (node (ref "Q2") (pin "6") (pinfunction "D_6") (pintype "passive"))
      (node (ref "R6") (pin "1") (pinfunction "1_1") (pintype "passive"))
    )
    (net (code "45") (name "/TIM1-CH4") (class "Default")
      (node (ref "R7") (pin "2") (pinfunction "2_2") (pintype "passive"))
      (node (ref "U1") (pin "44") (pinfunction "PA11_44") (pintype "bidirectional"))
    )
    (net (code "46") (name "/TIM1-CH4-K") (class "Default")
      (node (ref "J13") (pin "1") (pinfunction "1_1") (pintype "bidirectional"))
      (node (ref "Q2") (pin "3") (pinfunction "D_3") (pintype "passive"))
      (node (ref "R7") (pin "1") (pinfunction "1_1") (pintype "passive"))
    )
    (net (code "47") (name "/TIM3-CH1-RSSI") (class "Default")
      (node (ref "R12") (pin "1") (pinfunction "1_1") (pintype "passive"))
      (node (ref "TP3") (pin "1") (pinfunction "1_1") (pintype "bidirectional"))
      (node (ref "U1") (pin "22") (pinfunction "PA6_22") (pintype "bidirectional"))
      (node (ref "XBEE") (pin "6") (pinfunction "RSSI_6") (pintype "bidirectional"))
    )
    (net (code "48") (name "/TIM3-CH2-STSR") (class "Default")
      (node (ref "Q6") (pin "2") (pinfunction "G_2") (pintype "passive"))
      (node (ref "U1") (pin "23") (pinfunction "PA7_23") (pintype "bidirectional"))
    )
    (net (code "49") (name "/TIM3-CH3-STSG") (class "Default")
      (node (ref "Q3") (pin "5") (pinfunction "G_5") (pintype "passive"))
      (node (ref "U1") (pin "26") (pinfunction "PB0_26") (pintype "bidirectional"))
    )
    (net (code "50") (name "/TIM3-CH4-STSB") (class "Default")
      (node (ref "Q3") (pin "2") (pinfunction "G_2") (pintype "passive"))
      (node (ref "U1") (pin "27") (pinfunction "PB1_27") (pintype "bidirectional"))
    )
    (net (code "51") (name "/TIM4-CH1") (class "Default")
      (node (ref "R19") (pin "2") (pinfunction "2_2") (pintype "passive"))
      (node (ref "U1") (pin "58") (pinfunction "PB6_58") (pintype "bidirectional"))
    )
    (net (code "52") (name "/TIM4-CH1-K") (class "Default")
      (node (ref "J2") (pin "1") (pinfunction "1_1") (pintype "bidirectional"))
      (node (ref "Q4") (pin "6") (pinfunction "D_6") (pintype "passive"))
      (node (ref "R19") (pin "1") (pinfunction "1_1") (pintype "passive"))
    )
    (net (code "53") (name "/TIM4-CH2") (class "Default")
      (node (ref "R20") (pin "2") (pinfunction "2_2") (pintype "passive"))
      (node (ref "U1") (pin "59") (pinfunction "PB7_59") (pintype "bidirectional"))
    )
    (net (code "54") (name "/TIM4-CH2-K") (class "Default")
      (node (ref "J7") (pin "1") (pinfunction "1_1") (pintype "bidirectional"))
      (node (ref "Q4") (pin "3") (pinfunction "D_3") (pintype "passive"))
      (node (ref "R20") (pin "1") (pinfunction "1_1") (pintype "passive"))
    )
    (net (code "55") (name "/TIM4-CH3") (class "Default")
      (node (ref "R21") (pin "2") (pinfunction "2_2") (pintype "passive"))
      (node (ref "U1") (pin "61") (pinfunction "PB8_61") (pintype "bidirectional"))
    )
    (net (code "56") (name "/TIM4-CH3-K") (class "Default")
      (node (ref "J11") (pin "1") (pinfunction "1_1") (pintype "bidirectional"))
      (node (ref "Q5") (pin "6") (pinfunction "D_6") (pintype "passive"))
      (node (ref "R21") (pin "1") (pinfunction "1_1") (pintype "passive"))
    )
    (net (code "57") (name "/TIM4-CH4") (class "Default")
      (node (ref "R22") (pin "2") (pinfunction "2_2") (pintype "passive"))
      (node (ref "U1") (pin "62") (pinfunction "PB9_62") (pintype "bidirectional"))
    )
    (net (code "58") (name "/TIM4-CH4-K") (class "Default")
      (node (ref "J15") (pin "1") (pinfunction "1_1") (pintype "bidirectional"))
      (node (ref "Q5") (pin "3") (pinfunction "D_3") (pintype "passive"))
      (node (ref "R22") (pin "1") (pinfunction "1_1") (pintype "passive"))
    )
    (net (code "59") (name "/UART2-RX-XBEE") (class "Default")
      (node (ref "J17") (pin "2") (pinfunction "2_2") (pintype "bidirectional"))
      (node (ref "R10") (pin "1") (pinfunction "1_1") (pintype "passive"))
      (node (ref "U1") (pin "17") (pinfunction "PA3_17") (pintype "bidirectional"))
      (node (ref "XBEE") (pin "2") (pinfunction "DOUT_2") (pintype "output"))
    )
    (net (code "60") (name "/UART2-TX-XBEE") (class "Default")
      (node (ref "J17") (pin "1") (pinfunction "1_1") (pintype "bidirectional"))
      (node (ref "R2") (pin "1") (pinfunction "1_1") (pintype "passive"))
      (node (ref "U1") (pin "16") (pinfunction "PA2_16") (pintype "bidirectional"))
      (node (ref "XBEE") (pin "3") (pinfunction "DIN_3") (pintype "input"))
    )
    (net (code "61") (name "/UART4-RX") (class "Default")
      (node (ref "J20") (pin "2") (pinfunction "2_2") (pintype "bidirectional"))
      (node (ref "U1") (pin "15") (pinfunction "PA1_15") (pintype "bidirectional"))
    )
    (net (code "62") (name "/UART4-TX") (class "Default")
      (node (ref "J20") (pin "1") (pinfunction "1_1") (pintype "bidirectional"))
      (node (ref "U1") (pin "14") (pinfunction "PA0_WKUP_14") (pintype "bidirectional"))
    )
    (net (code "63") (name "/UART6-RX-GPS") (class "Default")
      (node (ref "J19") (pin "3") (pinfunction "3_3") (pintype "bidirectional"))
      (node (ref "U1") (pin "38") (pinfunction "PC7_38") (pintype "bidirectional"))
    )
    (net (code "64") (name "/UART6-TX-GPS") (class "Default")
      (node (ref "J19") (pin "2") (pinfunction "2_2") (pintype "bidirectional"))
      (node (ref "U1") (pin "37") (pinfunction "PC6_37") (pintype "bidirectional"))
    )
    (net (code "65") (name "/USD-CD") (class "Default")
      (node (ref "J23") (pin "CD") (pinfunction "CD-TERM_CD") (pintype "bidirectional"))
      (node (ref "R36") (pin "1") (pinfunction "1_1") (pintype "passive"))
      (node (ref "U1") (pin "33") (pinfunction "PB12_33") (pintype "bidirectional"))
    )
    (net (code "66") (name "3.3V") (class "Default")
      (node (ref "C10") (pin "2") (pinfunction "2_2") (pintype "passive"))
      (node (ref "C13") (pin "2") (pinfunction "2_2") (pintype "passive"))
      (node (ref "C14") (pin "2") (pinfunction "2_2") (pintype "passive"))
      (node (ref "C15") (pin "2") (pinfunction "2_2") (pintype "passive"))
      (node (ref "C16") (pin "2") (pinfunction "2_2") (pintype "passive"))
      (node (ref "C5") (pin "2") (pinfunction "2_2") (pintype "passive"))
      (node (ref "C6") (pin "2") (pinfunction "2_2") (pintype "passive"))
      (node (ref "C7") (pin "2") (pinfunction "2_2") (pintype "passive"))
      (node (ref "C8") (pin "2") (pinfunction "2_2") (pintype "passive"))
      (node (ref "C9") (pin "2") (pinfunction "2_2") (pintype "passive"))
      (node (ref "J23") (pin "4") (pinfunction "VCC_4") (pintype "bidirectional"))
      (node (ref "R1") (pin "1") (pinfunction "1_1") (pintype "passive"))
      (node (ref "R25") (pin "2") (pinfunction "2_2") (pintype "passive"))
      (node (ref "R3") (pin "2") (pinfunction "2_2") (pintype "passive"))
      (node (ref "R31") (pin "2") (pinfunction "2_2") (pintype "passive"))
      (node (ref "R33") (pin "2") (pinfunction "2_2") (pintype "passive"))
      (node (ref "R34") (pin "2") (pinfunction "2_2") (pintype "passive"))
      (node (ref "R36") (pin "2") (pinfunction "2_2") (pintype "passive"))
      (node (ref "U1") (pin "1") (pinfunction "VBAT_1") (pintype "power_in"))
      (node (ref "U1") (pin "13") (pinfunction "VDDA_13") (pintype "power_in"))
      (node (ref "U1") (pin "19") (pinfunction "VDD_19") (pintype "power_in"))
      (node (ref "U1") (pin "32") (pinfunction "VDD_32") (pintype "power_in"))
      (node (ref "U1") (pin "48") (pinfunction "VDD_48") (pintype "power_in"))
      (node (ref "U1") (pin "64") (pinfunction "VDD_64") (pintype "power_in"))
      (node (ref "U2") (pin "1") (pinfunction "VDD_1") (pintype "power_in"))
      (node (ref "U3") (pin "1") (pinfunction "RESV_1") (pintype "bidirectional"))
      (node (ref "U3") (pin "13") (pinfunction "VDD_13") (pintype "bidirectional"))
      (node (ref "U3") (pin "8") (pinfunction "VDDIO_8") (pintype "bidirectional"))
      (node (ref "U4") (pin "5") (pinfunction "OUT_5") (pintype "passive"))
      (node (ref "XBEE") (pin "1") (pinfunction "VDD_1") (pintype "power_in"))
    )
    (net (code "67") (name "5V") (class "Default")
      (node (ref "C3") (pin "2") (pinfunction "2_2") (pintype "passive"))
      (node (ref "J11") (pin "2") (pinfunction "2_2") (pintype "bidirectional"))
      (node (ref "J15") (pin "2") (pinfunction "2_2") (pintype "bidirectional"))
      (node (ref "J19") (pin "1") (pinfunction "1_1") (pintype "bidirectional"))
      (node (ref "J4") (pin "2") (pinfunction "2_2") (pintype "bidirectional"))
      (node (ref "J9") (pin "2") (pinfunction "2_2") (pintype "bidirectional"))
      (node (ref "Q7") (pin "1") (pinfunction "S_1") (pintype "passive"))
      (node (ref "Q7") (pin "2") (pinfunction "S_2") (pintype "passive"))
      (node (ref "Q7") (pin "3") (pinfunction "S_3") (pintype "passive"))
      (node (ref "R11") (pin "1") (pinfunction "1_1") (pintype "passive"))
      (node (ref "R13") (pin "1") (pinfunction "1_1") (pintype "passive"))
      (node (ref "R14") (pin "1") (pinfunction "1_1") (pintype "passive"))
      (node (ref "R16") (pin "1") (pinfunction "1_1") (pintype "passive"))
      (node (ref "R18") (pin "1") (pinfunction "1_1") (pintype "passive"))
      (node (ref "R8") (pin "1") (pinfunction "1_1") (pintype "passive"))
      (node (ref "R9") (pin "1") (pinfunction "1_1") (pintype "passive"))
      (node (ref "U4") (pin "1") (pinfunction "IN_1") (pintype "input"))
      (node (ref "U4") (pin "3") (pinfunction "EN_3") (pintype "input"))
    )
    (net (code "68") (name "5Vin") (class "Default")
      (node (ref "D1") (pin "C") (pinfunction "2_C") (pintype "passive"))
      (node (ref "J22") (pin "1") (pinfunction "VBUS_1") (pintype "bidirectional"))
      (node (ref "J5") (pin "1") (pinfunction "1_1") (pintype "bidirectional"))
      (node (ref "Q7") (pin "10") (pinfunction "D_10") (pintype "passive"))
      (node (ref "Q7") (pin "5") (pinfunction "D_5") (pintype "passive"))
      (node (ref "Q7") (pin "6") (pinfunction "D_6") (pintype "passive"))
      (node (ref "Q7") (pin "7") (pinfunction "D_7") (pintype "passive"))
      (node (ref "Q7") (pin "8") (pinfunction "D_8") (pintype "passive"))
      (node (ref "Q7") (pin "9") (pinfunction "D_9") (pintype "passive"))
    )
    (net (code "69") (name "GND") (class "Default")
      (node (ref "C1") (pin "1") (pinfunction "1_1") (pintype "passive"))
      (node (ref "C10") (pin "1") (pinfunction "1_1") (pintype "passive"))
      (node (ref "C11") (pin "1") (pinfunction "1_1") (pintype "passive"))
      (node (ref "C12") (pin "1") (pinfunction "1_1") (pintype "passive"))
      (node (ref "C13") (pin "1") (pinfunction "1_1") (pintype "passive"))
      (node (ref "C14") (pin "1") (pinfunction "1_1") (pintype "passive"))
      (node (ref "C15") (pin "1") (pinfunction "1_1") (pintype "passive"))
      (node (ref "C16") (pin "1") (pinfunction "1_1") (pintype "passive"))
      (node (ref "C17") (pin "1") (pinfunction "1_1") (pintype "passive"))
      (node (ref "C2") (pin "1") (pinfunction "1_1") (pintype "passive"))
      (node (ref "C3") (pin "1") (pinfunction "1_1") (pintype "passive"))
      (node (ref "C4") (pin "1") (pinfunction "1_1") (pintype "passive"))
      (node (ref "C5") (pin "1") (pinfunction "1_1") (pintype "passive"))
      (node (ref "C6") (pin "1") (pinfunction "1_1") (pintype "passive"))
      (node (ref "C7") (pin "1") (pinfunction "1_1") (pintype "passive"))
      (node (ref "C8") (pin "1") (pinfunction "1_1") (pintype "passive"))
      (node (ref "C9") (pin "1") (pinfunction "1_1") (pintype "passive"))
      (node (ref "D1") (pin "A") (pinfunction "1_A") (pintype "passive"))
      (node (ref "J1") (pin "2") (pinfunction "2_2") (pintype "bidirectional"))
      (node (ref "J10") (pin "2") (pinfunction "2_2") (pintype "bidirectional"))
      (node (ref "J11") (pin "3") (pinfunction "3_3") (pintype "bidirectional"))
      (node (ref "J12") (pin "2") (pinfunction "2_2") (pintype "bidirectional"))
      (node (ref "J13") (pin "2") (pinfunction "2_2") (pintype "bidirectional"))
      (node (ref "J14") (pin "2") (pinfunction "2_2") (pintype "bidirectional"))
      (node (ref "J15") (pin "3") (pinfunction "3_3") (pintype "bidirectional"))
      (node (ref "J16") (pin "3") (pinfunction "3_3") (pintype "bidirectional"))
      (node (ref "J17") (pin "3") (pinfunction "3_3") (pintype "bidirectional"))
      (node (ref "J18") (pin "4") (pinfunction "4_4") (pintype "bidirectional"))
      (node (ref "J19") (pin "4") (pinfunction "4_4") (pintype "bidirectional"))
      (node (ref "J2") (pin "2") (pinfunction "2_2") (pintype "bidirectional"))
      (node (ref "J20") (pin "3") (pinfunction "3_3") (pintype "bidirectional"))
      (node (ref "J21") (pin "4") (pinfunction "4_4") (pintype "bidirectional"))
      (node (ref "J22") (pin "5") (pinfunction "GND_5") (pintype "bidirectional"))
      (node (ref "J22") (pin "S1A") (pinfunction "S1_S1A") (pintype "bidirectional"))
      (node (ref "J22") (pin "S1B") (pinfunction "S1_S1B") (pintype "bidirectional"))
      (node (ref "J22") (pin "S2A") (pinfunction "S2_S2A") (pintype "bidirectional"))
      (node (ref "J22") (pin "S2B") (pinfunction "S2_S2B") (pintype "bidirectional"))
      (node (ref "J22") (pin "S3") (pinfunction "S3_S3") (pintype "bidirectional"))
      (node (ref "J22") (pin "S4") (pinfunction "S4_S4") (pintype "bidirectional"))
      (node (ref "J23") (pin "6") (pinfunction "GND_6") (pintype "bidirectional"))
      (node (ref "J23") (pin "GND") (pinfunction "GND-TERM_GND") (pintype "bidirectional"))
      (node (ref "J23") (pin "S1") (pinfunction "SHIELD_S1") (pintype "bidirectional"))
      (node (ref "J23") (pin "S2") (pinfunction "SHIELD_S2") (pintype "bidirectional"))
      (node (ref "J23") (pin "S3") (pinfunction "SHIELD_S3") (pintype "bidirectional"))
      (node (ref "J23") (pin "S4") (pinfunction "SHIELD_S4") (pintype "bidirectional"))
      (node (ref "J23") (pin "S5") (pinfunction "SHIELD_S5") (pintype "bidirectional"))
      (node (ref "J3") (pin "2") (pinfunction "2_2") (pintype "bidirectional"))
      (node (ref "J4") (pin "3") (pinfunction "3_3") (pintype "bidirectional"))
      (node (ref "J5") (pin "2") (pinfunction "2_2") (pintype "bidirectional"))
      (node (ref "J6") (pin "2") (pinfunction "2_2") (pintype "bidirectional"))
      (node (ref "J7") (pin "2") (pinfunction "2_2") (pintype "bidirectional"))
      (node (ref "J8") (pin "2") (pinfunction "2_2") (pintype "bidirectional"))
      (node (ref "J9") (pin "3") (pinfunction "3_3") (pintype "bidirectional"))
      (node (ref "LED1") (pin "C") (pinfunction "C_C") (pintype "passive"))
      (node (ref "LED10") (pin "C") (pinfunction "C_C") (pintype "passive"))
      (node (ref "LED11") (pin "C") (pinfunction "C_C") (pintype "passive"))
      (node (ref "LED2") (pin "C") (pinfunction "C_C") (pintype "passive"))
      (node (ref "LED3") (pin "C") (pinfunction "C_C") (pintype "passive"))
      (node (ref "LED4") (pin "C") (pinfunction "C_C") (pintype "passive"))
      (node (ref "LED6") (pin "C") (pinfunction "C_C") (pintype "passive"))
      (node (ref "LED7") (pin "C") (pinfunction "C_C") (pintype "passive"))
      (node (ref "LED9") (pin "C") (pinfunction "C_C") (pintype "passive"))
      (node (ref "Q1") (pin "1") (pinfunction "S_1") (pintype "passive"))
      (node (ref "Q1") (pin "4") (pinfunction "S_4") (pintype "passive"))
      (node (ref "Q2") (pin "1") (pinfunction "S_1") (pintype "passive"))
      (node (ref "Q2") (pin "4") (pinfunction "S_4") (pintype "passive"))
      (node (ref "Q3") (pin "1") (pinfunction "S_1") (pintype "passive"))
      (node (ref "Q3") (pin "4") (pinfunction "S_4") (pintype "passive"))
      (node (ref "Q4") (pin "1") (pinfunction "S_1") (pintype "passive"))
      (node (ref "Q4") (pin "4") (pinfunction "S_4") (pintype "passive"))
      (node (ref "Q5") (pin "1") (pinfunction "S_1") (pintype "passive"))
      (node (ref "Q5") (pin "4") (pinfunction "S_4") (pintype "passive"))
      (node (ref "Q6") (pin "1") (pinfunction "S_1") (pintype "passive"))
      (node (ref "Q7") (pin "4") (pinfunction "G_4") (pintype "passive"))
      (node (ref "R27") (pin "2") (pinfunction "2_2") (pintype "passive"))
      (node (ref "R29") (pin "2") (pinfunction "2_2") (pintype "passive"))
      (node (ref "R30") (pin "2") (pinfunction "2_2") (pintype "passive"))
      (node (ref "R32") (pin "2") (pinfunction "2_2") (pintype "passive"))
      (node (ref "S1") (pin "3") (pinfunction "2_3") (pintype "passive"))
      (node (ref "S1") (pin "4") (pinfunction "2_4") (pintype "passive"))
      (node (ref "S2") (pin "P1") (pinfunction "P$1_P1") (pintype "bidirectional"))
      (node (ref "S3") (pin "P1") (pinfunction "P$1_P1") (pintype "bidirectional"))
      (node (ref "S4") (pin "P1") (pinfunction "P$1_P1") (pintype "bidirectional"))
      (node (ref "S5") (pin "P1") (pinfunction "P$1_P1") (pintype "bidirectional"))
      (node (ref "U1") (pin "12") (pinfunction "VSSA_12") (pintype "power_in"))
      (node (ref "U1") (pin "18") (pinfunction "VSS_18") (pintype "power_in"))
      (node (ref "U1") (pin "63") (pinfunction "VSS_63") (pintype "power_in"))
      (node (ref "U2") (pin "2") (pinfunction "PS_2") (pintype "input"))
      (node (ref "U2") (pin "3") (pinfunction "GND_3") (pintype "power_in"))
      (node (ref "U3") (pin "11") (pinfunction "FSYNC_11") (pintype "bidirectional"))
      (node (ref "U3") (pin "18") (pinfunction "GND_18") (pintype "bidirectional"))
      (node (ref "U3") (pin "20") (pinfunction "RESV_20") (pintype "bidirectional"))
      (node (ref "U4") (pin "2") (pinfunction "GND_2") (pintype "input"))
      (node (ref "XBEE") (pin "10") (pinfunction "GND_10") (pintype "power_in"))
    )
    (net (code "70") (name "Net-(J4-Pad1)") (class "Default")
      (node (ref "J4") (pin "1") (pinfunction "1_1") (pintype "bidirectional"))
      (node (ref "R26") (pin "2") (pinfunction "2_2") (pintype "passive"))
    )
    (net (code "71") (name "Net-(J9-Pad1)") (class "Default")
      (node (ref "J9") (pin "1") (pinfunction "1_1") (pintype "bidirectional"))
      (node (ref "R28") (pin "2") (pinfunction "2_2") (pintype "passive"))
    )
    (net (code "72") (name "Net-(LED1-PadA)") (class "Default")
      (node (ref "LED1") (pin "A") (pinfunction "A_A") (pintype "passive"))
      (node (ref "R1") (pin "2") (pinfunction "2_2") (pintype "passive"))
    )
    (net (code "73") (name "Net-(LED2-PadA)") (class "Default")
      (node (ref "LED2") (pin "A") (pinfunction "A_A") (pintype "passive"))
      (node (ref "R2") (pin "2") (pinfunction "2_2") (pintype "passive"))
    )
    (net (code "74") (name "Net-(LED3-PadA)") (class "Default")
      (node (ref "LED3") (pin "A") (pinfunction "A_A") (pintype "passive"))
      (node (ref "R9") (pin "2") (pinfunction "2_2") (pintype "passive"))
    )
    (net (code "75") (name "Net-(LED4-PadA)") (class "Default")
      (node (ref "LED4") (pin "A") (pinfunction "A_A") (pintype "passive"))
      (node (ref "R10") (pin "2") (pinfunction "2_2") (pintype "passive"))
    )
    (net (code "76") (name "Net-(LED5-B+)") (class "Default")
      (node (ref "LED5") (pin "A1") (pinfunction "B+_A1") (pintype "passive"))
      (node (ref "R13") (pin "2") (pinfunction "2_2") (pintype "passive"))
    )
    (net (code "77") (name "Net-(LED5-B-)") (class "Default")
      (node (ref "LED5") (pin "C1") (pinfunction "B-_C1") (pintype "passive"))
      (node (ref "LED8") (pin "C1") (pinfunction "B-_C1") (pintype "passive"))
      (node (ref "Q3") (pin "6") (pinfunction "D_6") (pintype "passive"))
    )
    (net (code "78") (name "Net-(LED5-G+)") (class "Default")
      (node (ref "LED5") (pin "A3") (pinfunction "G+_A3") (pintype "passive"))
      (node (ref "R11") (pin "2") (pinfunction "2_2") (pintype "passive"))
    )
    (net (code "79") (name "Net-(LED5-G-)") (class "Default")
      (node (ref "LED5") (pin "C3") (pinfunction "G-_C3") (pintype "passive"))
      (node (ref "LED8") (pin "C3") (pinfunction "G-_C3") (pintype "passive"))
      (node (ref "Q3") (pin "3") (pinfunction "D_3") (pintype "passive"))
    )
    (net (code "80") (name "Net-(LED5-R+)") (class "Default")
      (node (ref "LED5") (pin "A2") (pinfunction "R+_A2") (pintype "passive"))
      (node (ref "R8") (pin "2") (pinfunction "2_2") (pintype "passive"))
    )
    (net (code "81") (name "Net-(LED5-R-)") (class "Default")
      (node (ref "LED5") (pin "C2") (pinfunction "R-_C2") (pintype "passive"))
      (node (ref "LED8") (pin "C2") (pinfunction "R-_C2") (pintype "passive"))
      (node (ref "Q6") (pin "6") (pinfunction "D_6") (pintype "passive"))
    )
    (net (code "82") (name "Net-(LED6-PadA)") (class "Default")
      (node (ref "LED6") (pin "A") (pinfunction "A_A") (pintype "passive"))
      (node (ref "R12") (pin "2") (pinfunction "2_2") (pintype "passive"))
    )
    (net (code "83") (name "Net-(LED7-PadA)") (class "Default")
      (node (ref "LED7") (pin "A") (pinfunction "A_A") (pintype "passive"))
      (node (ref "R15") (pin "2") (pinfunction "2_2") (pintype "passive"))
    )
    (net (code "84") (name "Net-(LED8-B+)") (class "Default")
      (node (ref "LED8") (pin "A1") (pinfunction "B+_A1") (pintype "passive"))
      (node (ref "R18") (pin "2") (pinfunction "2_2") (pintype "passive"))
    )
    (net (code "85") (name "Net-(LED8-G+)") (class "Default")
      (node (ref "LED8") (pin "A3") (pinfunction "G+_A3") (pintype "passive"))
      (node (ref "R16") (pin "2") (pinfunction "2_2") (pintype "passive"))
    )
    (net (code "86") (name "Net-(LED8-R+)") (class "Default")
      (node (ref "LED8") (pin "A2") (pinfunction "R+_A2") (pintype "passive"))
      (node (ref "R14") (pin "2") (pinfunction "2_2") (pintype "passive"))
    )
    (net (code "87") (name "Net-(LED9-PadA)") (class "Default")
      (node (ref "LED9") (pin "A") (pinfunction "A_A") (pintype "passive"))
      (node (ref "R17") (pin "2") (pinfunction "2_2") (pintype "passive"))
    )
    (net (code "88") (name "Net-(LED10-PadA)") (class "Default")
      (node (ref "LED10") (pin "A") (pinfunction "A_A") (pintype "passive"))
      (node (ref "R23") (pin "2") (pinfunction "2_2") (pintype "passive"))
    )
    (net (code "89") (name "Net-(LED11-PadA)") (class "Default")
      (node (ref "LED11") (pin "A") (pinfunction "A_A") (pintype "passive"))
      (node (ref "R24") (pin "2") (pinfunction "2_2") (pintype "passive"))
    )
    (net (code "90") (name "Net-(U1B-VCAP_1)") (class "Default")
      (node (ref "C12") (pin "2") (pinfunction "2_2") (pintype "passive"))
      (node (ref "U1") (pin "31") (pinfunction "VCAP_1_31") (pintype "passive"))
    )
    (net (code "91") (name "Net-(U1B-VCAP_2)") (class "Default")
      (node (ref "C11") (pin "2") (pinfunction "2_2") (pintype "passive"))
      (node (ref "U1") (pin "47") (pinfunction "VCAP_2_47") (pintype "passive"))
    )
    (net (code "92") (name "Net-(U4-BP)") (class "Default")
      (node (ref "C4") (pin "2") (pinfunction "2_2") (pintype "passive"))
      (node (ref "U4") (pin "4") (pinfunction "BP_4") (pintype "input"))
    )
    (net (code "93") (name "unconnected-(U3-AUX_CL-Pad7)") (class "Default")
      (node (ref "U3") (pin "7") (pinfunction "AUX_CL_7") (pintype "bidirectional"))
    )
    (net (code "94") (name "unconnected-(U3-AUX_DA-Pad21)") (class "Default")
      (node (ref "U3") (pin "21") (pinfunction "AUX_DA_21") (pintype "bidirectional"))
    )
    (net (code "95") (name "unconnected-(U3-INT-Pad12)") (class "Default")
      (node (ref "U3") (pin "12") (pinfunction "INT_12") (pintype "bidirectional"))
    )
    (net (code "96") (name "unconnected-(XBEE-CTS-Pad12)") (class "Default")
      (node (ref "XBEE") (pin "12") (pinfunction "CTS_12") (pintype "output"))
    )
    (net (code "97") (name "unconnected-(XBEE-DIO1-Pad19)") (class "Default")
      (node (ref "XBEE") (pin "19") (pinfunction "DIO1_19") (pintype "bidirectional"))
    )
    (net (code "98") (name "unconnected-(XBEE-DIO2-Pad18)") (class "Default")
      (node (ref "XBEE") (pin "18") (pinfunction "DIO2_18") (pintype "bidirectional"))
    )
    (net (code "99") (name "unconnected-(XBEE-DIO3-Pad17)") (class "Default")
      (node (ref "XBEE") (pin "17") (pinfunction "DIO3_17") (pintype "bidirectional"))
    )
    (net (code "100") (name "unconnected-(XBEE-DIO4-Pad11)") (class "Default")
      (node (ref "XBEE") (pin "11") (pinfunction "DIO4_11") (pintype "bidirectional"))
    )
    (net (code "101") (name "unconnected-(XBEE-DIO5-Pad15)") (class "Default")
      (node (ref "XBEE") (pin "15") (pinfunction "DIO5_15") (pintype "bidirectional"))
    )
    (net (code "102") (name "unconnected-(XBEE-DIO9-Pad13)") (class "Default")
      (node (ref "XBEE") (pin "13") (pinfunction "DIO9_13") (pintype "bidirectional"))
    )
    (net (code "103") (name "unconnected-(XBEE-DIO11-Pad7)") (class "Default")
      (node (ref "XBEE") (pin "7") (pinfunction "DIO11_7") (pintype "bidirectional"))
    )
    (net (code "104") (name "unconnected-(XBEE-DIO12-Pad4)") (class "Default")
      (node (ref "XBEE") (pin "4") (pinfunction "DIO12_4") (pintype "bidirectional"))
    )
    (net (code "105") (name "unconnected-(XBEE-DTR-Pad9)") (class "Default")
      (node (ref "XBEE") (pin "9") (pinfunction "DTR_9") (pintype "bidirectional"))
    )
    (net (code "106") (name "unconnected-(XBEE-RES-Pad8)") (class "Default")
      (node (ref "XBEE") (pin "8") (pinfunction "RES_8") (pintype "bidirectional"))
    )
    (net (code "107") (name "unconnected-(XBEE-RES-Pad14)") (class "Default")
      (node (ref "XBEE") (pin "14") (pinfunction "RES_14") (pintype "bidirectional"))
    )
    (net (code "108") (name "unconnected-(XBEE-RESET-Pad5)") (class "Default")
      (node (ref "XBEE") (pin "5") (pinfunction "RESET_5") (pintype "input"))
    )
    (net (code "109") (name "unconnected-(XBEE-RTS-Pad16)") (class "Default")
      (node (ref "XBEE") (pin "16") (pinfunction "RTS_16") (pintype "input"))
    )
  )
)
